# Sheet1.net
KiCad netlist of a schematic drawn in Altium Designer
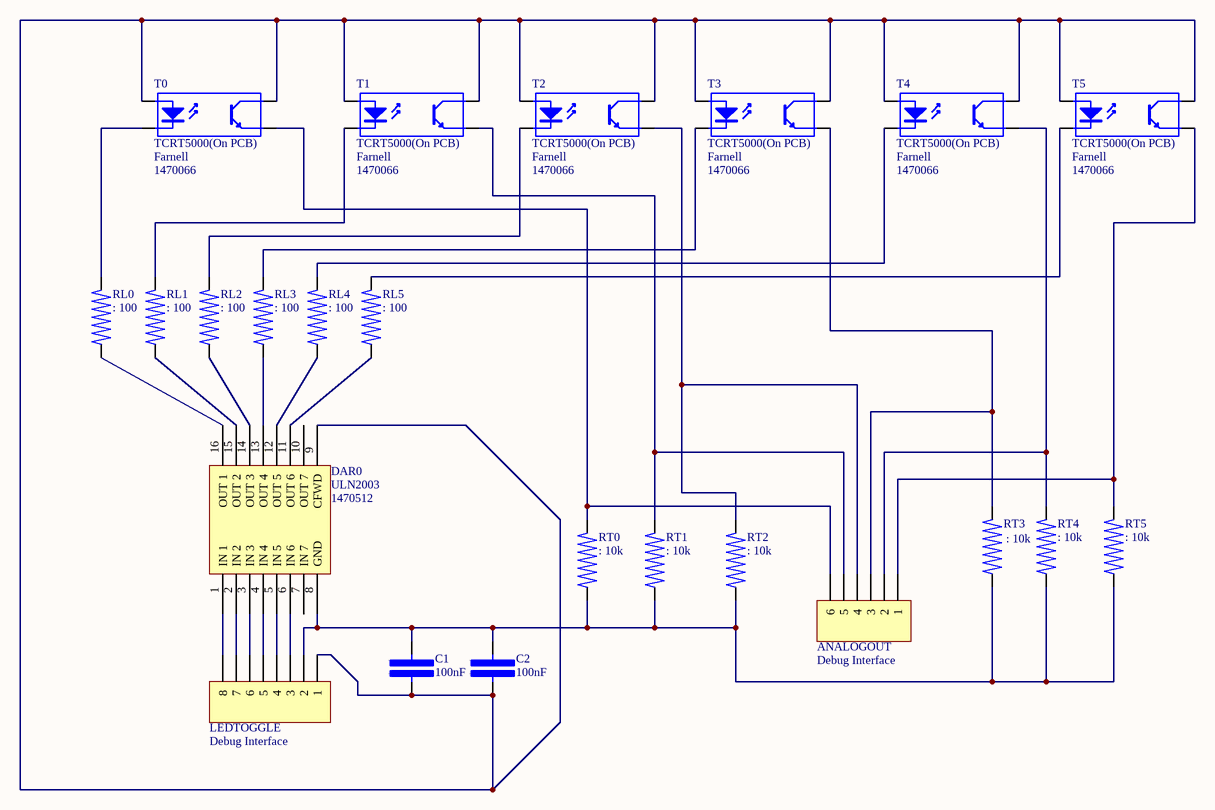
[diagram p0: Sheet1.SchDoc]

(export (version "E")
  (design (tool "Eeschema 10.0.6"))
  (components
    (comp (ref "ANALOGOUT")
      (value "Debug Interface")
      (footprint "PROGRAMMING-HEADER-MICRO")
      (description "Header, 6-Pin")
      (fields (field (name "PUBLISHER") "Altium Limited"))
      (libsource (lib "Integrated_Library") (part "Header 6"))
    )
    (comp (ref "C1")
      (value "100nF")
      (footprint "CAPACITOR_100NF_TH")
      (description "Capacitor 100nF")
      (libsource (lib "Integrated_Library") (part "Capacitor(IO Board)"))
    )
    (comp (ref "C2")
      (value "100nF")
      (footprint "CAPACITOR_100NF_TH")
      (description "Capacitor 100nF")
      (libsource (lib "Integrated_Library") (part "Capacitor(IO Board)"))
    )
    (comp (ref "DAR0")
      (value "ULN2003")
      (footprint "DILP-16(300) - 3D")
      (description "Darlington Transistor Array")
      (fields (field (name "SUPPLIER PART NUMBER 1") "1470512"))
      (libsource (lib "Integrated_Library") (part "ULN2003"))
    )
    (comp (ref "LEDTOGGLE")
      (value "Debug Interface")
      (footprint "HDR1X8")
      (description "Header, 8-Pin")
      (fields (field (name "PUBLISHER") "Altium Limited"))
      (libsource (lib "Miscellaneous Connectors") (part "Header 8"))
    )
    (comp (ref "RL0")
      (value "Resistor (IO board)")
      (footprint "RESISTOR_10K_TH_QW")
      (description "Resistor (SFR25)")
      (fields (field (name "ALTIUM_UNNAMED_1") "100"))
      (libsource (lib "Integrated_Library") (part "Resistor(IO board)"))
    )
    (comp (ref "RL1")
      (value "Resistor (IO board)")
      (footprint "RESISTOR_10K_TH_QW")
      (description "Resistor (SFR25)")
      (fields (field (name "ALTIUM_UNNAMED_1") "100"))
      (libsource (lib "Integrated_Library") (part "Resistor(IO board)"))
    )
    (comp (ref "RL2")
      (value "Resistor (IO board)")
      (footprint "RESISTOR_10K_TH_QW")
      (description "Resistor (SFR25)")
      (fields (field (name "ALTIUM_UNNAMED_1") "100"))
      (libsource (lib "Integrated_Library") (part "Resistor(IO board)"))
    )
    (comp (ref "RL3")
      (value "Resistor (IO board)")
      (footprint "RESISTOR_10K_TH_QW")
      (description "Resistor (SFR25)")
      (fields (field (name "ALTIUM_UNNAMED_1") "100"))
      (libsource (lib "Integrated_Library") (part "Resistor(IO board)"))
    )
    (comp (ref "RL4")
      (value "Resistor (IO board)")
      (footprint "RESISTOR_10K_TH_QW")
      (description "Resistor (SFR25)")
      (fields (field (name "ALTIUM_UNNAMED_1") "100"))
      (libsource (lib "Integrated_Library") (part "Resistor(IO board)"))
    )
    (comp (ref "RL5")
      (value "Resistor (IO board)")
      (footprint "RESISTOR_10K_TH_QW")
      (description "Resistor (SFR25)")
      (fields (field (name "ALTIUM_UNNAMED_1") "100"))
      (libsource (lib "Integrated_Library") (part "Resistor(IO board)"))
    )
    (comp (ref "RT0")
      (value "Resistor (IO board)")
      (footprint "RESISTOR_10K_TH_QW")
      (description "Resistor (SFR25)")
      (fields (field (name "ALTIUM_UNNAMED_1") "10k"))
      (libsource (lib "Integrated_Library") (part "Resistor(IO board)"))
    )
    (comp (ref "RT1")
      (value "Resistor (IO board)")
      (footprint "RESISTOR_10K_TH_QW")
      (description "Resistor (SFR25)")
      (fields (field (name "ALTIUM_UNNAMED_1") "10k"))
      (libsource (lib "Integrated_Library") (part "Resistor(IO board)"))
    )
    (comp (ref "RT2")
      (value "Resistor (IO board)")
      (footprint "RESISTOR_10K_TH_QW")
      (description "Resistor (SFR25)")
      (fields (field (name "ALTIUM_UNNAMED_1") "10k"))
      (libsource (lib "Integrated_Library") (part "Resistor(IO board)"))
    )
    (comp (ref "RT3")
      (value "Resistor (IO board)")
      (footprint "RESISTOR_10K_TH_QW")
      (description "Resistor (SFR25)")
      (fields (field (name "ALTIUM_UNNAMED_1") "10k"))
      (libsource (lib "Integrated_Library") (part "Resistor(IO board)"))
    )
    (comp (ref "RT4")
      (value "Resistor (IO board)")
      (footprint "RESISTOR_10K_TH_QW")
      (description "Resistor (SFR25)")
      (fields (field (name "ALTIUM_UNNAMED_1") "10k"))
      (libsource (lib "Integrated_Library") (part "Resistor(IO board)"))
    )
    (comp (ref "RT5")
      (value "Resistor (IO board)")
      (footprint "RESISTOR_10K_TH_QW")
      (description "Resistor (SFR25)")
      (fields (field (name "ALTIUM_UNNAMED_1") "10k"))
      (libsource (lib "Integrated_Library") (part "Resistor(IO board)"))
    )
    (comp (ref "T0")
      (value "TCRT5000(On PCB)")
      (footprint "TCRT5000 Breakout")
      (description "4-Pin Phototransistor Optocoupler")
      (fields
        (field (name "SUPPLIER 1") "Farnell")
        (field (name "SUPPLIER PART NUMBER 1") "1470066")
        (field (name "PUBLISHER") "Altium Limited")
      )
      (libsource (lib "Integrated_Library") (part "TCRT5000(On PCB)"))
    )
    (comp (ref "T1")
      (value "TCRT5000(On PCB)")
      (footprint "TCRT5000 Breakout")
      (description "4-Pin Phototransistor Optocoupler")
      (fields
        (field (name "SUPPLIER 1") "Farnell")
        (field (name "SUPPLIER PART NUMBER 1") "1470066")
        (field (name "PUBLISHER") "Altium Limited")
      )
      (libsource (lib "Integrated_Library") (part "TCRT5000(On PCB)"))
    )
    (comp (ref "T2")
      (value "TCRT5000(On PCB)")
      (footprint "TCRT5000 Breakout")
      (description "4-Pin Phototransistor Optocoupler")
      (fields
        (field (name "SUPPLIER 1") "Farnell")
        (field (name "SUPPLIER PART NUMBER 1") "1470066")
        (field (name "PUBLISHER") "Altium Limited")
      )
      (libsource (lib "Integrated_Library") (part "TCRT5000(On PCB)"))
    )
    (comp (ref "T3")
      (value "TCRT5000(On PCB)")
      (footprint "TCRT5000 Breakout")
      (description "4-Pin Phototransistor Optocoupler")
      (fields
        (field (name "SUPPLIER 1") "Farnell")
        (field (name "SUPPLIER PART NUMBER 1") "1470066")
        (field (name "PUBLISHER") "Altium Limited")
      )
      (libsource (lib "Integrated_Library") (part "TCRT5000(On PCB)"))
    )
    (comp (ref "T4")
      (value "TCRT5000(On PCB)")
      (footprint "TCRT5000 Breakout")
      (description "4-Pin Phototransistor Optocoupler")
      (fields
        (field (name "SUPPLIER 1") "Farnell")
        (field (name "SUPPLIER PART NUMBER 1") "1470066")
        (field (name "PUBLISHER") "Altium Limited")
      )
      (libsource (lib "Integrated_Library") (part "TCRT5000(On PCB)"))
    )
    (comp (ref "T5")
      (value "TCRT5000(On PCB)")
      (footprint "TCRT5000 Breakout")
      (description "4-Pin Phototransistor Optocoupler")
      (fields
        (field (name "SUPPLIER 1") "Farnell")
        (field (name "SUPPLIER PART NUMBER 1") "1470066")
        (field (name "PUBLISHER") "Altium Limited")
      )
      (libsource (lib "Integrated_Library") (part "TCRT5000(On PCB)"))
    )
  )
  (nets
    (net (code "1") (name "Net-(DAR0-CFWD)") (class "Default")
      (node (ref "C1") (pin "1") (pinfunction "1_1") (pintype "passive"))
      (node (ref "C2") (pin "1") (pinfunction "1_1") (pintype "passive"))
      (node (ref "DAR0") (pin "9") (pinfunction "CFWD_9") (pintype "passive"))
      (node (ref "LEDTOGGLE") (pin "1") (pinfunction "1_1") (pintype "passive"))
      (node (ref "T0") (pin "1") (pinfunction "A_1") (pintype "passive"))
      (node (ref "T0") (pin "4") (pinfunction "C_4") (pintype "passive"))
      (node (ref "T1") (pin "1") (pinfunction "A_1") (pintype "passive"))
      (node (ref "T1") (pin "4") (pinfunction "C_4") (pintype "passive"))
      (node (ref "T2") (pin "1") (pinfunction "A_1") (pintype "passive"))
      (node (ref "T2") (pin "4") (pinfunction "C_4") (pintype "passive"))
      (node (ref "T3") (pin "1") (pinfunction "A_1") (pintype "passive"))
      (node (ref "T3") (pin "4") (pinfunction "C_4") (pintype "passive"))
      (node (ref "T4") (pin "1") (pinfunction "A_1") (pintype "passive"))
      (node (ref "T4") (pin "4") (pinfunction "C_4") (pintype "passive"))
      (node (ref "T5") (pin "1") (pinfunction "A_1") (pintype "passive"))
      (node (ref "T5") (pin "4") (pinfunction "C_4") (pintype "passive"))
    )
    (net (code "2") (name "Net-(DAR0-GND)") (class "Default")
      (node (ref "C1") (pin "2") (pinfunction "2_2") (pintype "passive"))
      (node (ref "C2") (pin "2") (pinfunction "2_2") (pintype "passive"))
      (node (ref "DAR0") (pin "8") (pinfunction "GND_8") (pintype "passive"))
      (node (ref "LEDTOGGLE") (pin "2") (pinfunction "2_2") (pintype "passive"))
      (node (ref "RT0") (pin "1") (pinfunction "1_1") (pintype "passive"))
      (node (ref "RT1") (pin "1") (pinfunction "1_1") (pintype "passive"))
      (node (ref "RT2") (pin "1") (pinfunction "1_1") (pintype "passive"))
      (node (ref "RT3") (pin "1") (pinfunction "1_1") (pintype "passive"))
      (node (ref "RT4") (pin "1") (pinfunction "1_1") (pintype "passive"))
      (node (ref "RT5") (pin "1") (pinfunction "1_1") (pintype "passive"))
    )
    (net (code "3") (name "Net-(DAR0-IN_1)") (class "Default")
      (node (ref "DAR0") (pin "1") (pinfunction "IN_1_1") (pintype "passive"))
      (node (ref "LEDTOGGLE") (pin "8") (pinfunction "8_8") (pintype "passive"))
    )
    (net (code "4") (name "Net-(DAR0-IN_2)") (class "Default")
      (node (ref "DAR0") (pin "2") (pinfunction "IN_2_2") (pintype "passive"))
      (node (ref "LEDTOGGLE") (pin "7") (pinfunction "7_7") (pintype "passive"))
    )
    (net (code "5") (name "Net-(DAR0-IN_3)") (class "Default")
      (node (ref "DAR0") (pin "3") (pinfunction "IN_3_3") (pintype "passive"))
      (node (ref "LEDTOGGLE") (pin "6") (pinfunction "6_6") (pintype "passive"))
    )
    (net (code "6") (name "Net-(DAR0-IN_4)") (class "Default")
      (node (ref "DAR0") (pin "4") (pinfunction "IN_4_4") (pintype "passive"))
      (node (ref "LEDTOGGLE") (pin "5") (pinfunction "5_5") (pintype "passive"))
    )
    (net (code "7") (name "Net-(DAR0-IN_5)") (class "Default")
      (node (ref "DAR0") (pin "5") (pinfunction "IN_5_5") (pintype "passive"))
      (node (ref "LEDTOGGLE") (pin "4") (pinfunction "4_4") (pintype "passive"))
    )
    (net (code "8") (name "Net-(DAR0-IN_6)") (class "Default")
      (node (ref "DAR0") (pin "6") (pinfunction "IN_6_6") (pintype "passive"))
      (node (ref "LEDTOGGLE") (pin "3") (pinfunction "3_3") (pintype "passive"))
    )
    (net (code "9") (name "Net-(DAR0-OUT_1)") (class "Default")
      (node (ref "DAR0") (pin "16") (pinfunction "OUT_1_16") (pintype "passive"))
      (node (ref "RL0") (pin "1") (pinfunction "1_1") (pintype "passive"))
    )
    (net (code "10") (name "Net-(DAR0-OUT_2)") (class "Default")
      (node (ref "DAR0") (pin "15") (pinfunction "OUT_2_15") (pintype "passive"))
      (node (ref "RL1") (pin "1") (pinfunction "1_1") (pintype "passive"))
    )
    (net (code "11") (name "Net-(DAR0-OUT_3)") (class "Default")
      (node (ref "DAR0") (pin "14") (pinfunction "OUT_3_14") (pintype "passive"))
      (node (ref "RL2") (pin "1") (pinfunction "1_1") (pintype "passive"))
    )
    (net (code "12") (name "Net-(DAR0-OUT_4)") (class "Default")
      (node (ref "DAR0") (pin "13") (pinfunction "OUT_4_13") (pintype "passive"))
      (node (ref "RL3") (pin "1") (pinfunction "1_1") (pintype "passive"))
    )
    (net (code "13") (name "Net-(DAR0-OUT_5)") (class "Default")
      (node (ref "DAR0") (pin "12") (pinfunction "OUT_5_12") (pintype "passive"))
      (node (ref "RL4") (pin "1") (pinfunction "1_1") (pintype "passive"))
    )
    (net (code "14") (name "Net-(DAR0-OUT_6)") (class "Default")
      (node (ref "DAR0") (pin "11") (pinfunction "OUT_6_11") (pintype "passive"))
      (node (ref "RL5") (pin "1") (pinfunction "1_1") (pintype "passive"))
    )
    (net (code "15") (name "Net-(T0-E)") (class "Default")
      (node (ref "ANALOGOUT") (pin "6") (pinfunction "6_6") (pintype "passive"))
      (node (ref "RT0") (pin "2") (pinfunction "2_2") (pintype "passive"))
      (node (ref "T0") (pin "3") (pinfunction "E_3") (pintype "passive"))
    )
    (net (code "16") (name "Net-(T0-K)") (class "Default")
      (node (ref "RL0") (pin "2") (pinfunction "2_2") (pintype "passive"))
      (node (ref "T0") (pin "2") (pinfunction "K_2") (pintype "passive"))
    )
    (net (code "17") (name "Net-(T1-E)") (class "Default")
      (node (ref "ANALOGOUT") (pin "5") (pinfunction "5_5") (pintype "passive"))
      (node (ref "RT1") (pin "2") (pinfunction "2_2") (pintype "passive"))
      (node (ref "T1") (pin "3") (pinfunction "E_3") (pintype "passive"))
    )
    (net (code "18") (name "Net-(T1-K)") (class "Default")
      (node (ref "RL1") (pin "2") (pinfunction "2_2") (pintype "passive"))
      (node (ref "T1") (pin "2") (pinfunction "K_2") (pintype "passive"))
    )
    (net (code "19") (name "Net-(T2-E)") (class "Default")
      (node (ref "ANALOGOUT") (pin "4") (pinfunction "4_4") (pintype "passive"))
      (node (ref "RT2") (pin "2") (pinfunction "2_2") (pintype "passive"))
      (node (ref "T2") (pin "3") (pinfunction "E_3") (pintype "passive"))
    )
    (net (code "20") (name "Net-(T2-K)") (class "Default")
      (node (ref "RL2") (pin "2") (pinfunction "2_2") (pintype "passive"))
      (node (ref "T2") (pin "2") (pinfunction "K_2") (pintype "passive"))
    )
    (net (code "21") (name "Net-(T3-E)") (class "Default")
      (node (ref "ANALOGOUT") (pin "3") (pinfunction "3_3") (pintype "passive"))
      (node (ref "RT3") (pin "2") (pinfunction "2_2") (pintype "passive"))
      (node (ref "T3") (pin "3") (pinfunction "E_3") (pintype "passive"))
    )
    (net (code "22") (name "Net-(T3-K)") (class "Default")
      (node (ref "RL3") (pin "2") (pinfunction "2_2") (pintype "passive"))
      (node (ref "T3") (pin "2") (pinfunction "K_2") (pintype "passive"))
    )
    (net (code "23") (name "Net-(T4-E)") (class "Default")
      (node (ref "ANALOGOUT") (pin "2") (pinfunction "2_2") (pintype "passive"))
      (node (ref "RT4") (pin "2") (pinfunction "2_2") (pintype "passive"))
      (node (ref "T4") (pin "3") (pinfunction "E_3") (pintype "passive"))
    )
    (net (code "24") (name "Net-(T4-K)") (class "Default")
      (node (ref "RL4") (pin "2") (pinfunction "2_2") (pintype "passive"))
      (node (ref "T4") (pin "2") (pinfunction "K_2") (pintype "passive"))
    )
    (net (code "25") (name "Net-(T5-E)") (class "Default")
      (node (ref "ANALOGOUT") (pin "1") (pinfunction "1_1") (pintype "passive"))
      (node (ref "RT5") (pin "2") (pinfunction "2_2") (pintype "passive"))
      (node (ref "T5") (pin "3") (pinfunction "E_3") (pintype "passive"))
    )
    (net (code "26") (name "Net-(T5-K)") (class "Default")
      (node (ref "RL5") (pin "2") (pinfunction "2_2") (pintype "passive"))
      (node (ref "T5") (pin "2") (pinfunction "K_2") (pintype "passive"))
    )
    (net (code "27") (name "unconnected-(DAR0-IN_7-Pad7)") (class "Default")
      (node (ref "DAR0") (pin "7") (pinfunction "IN_7_7") (pintype "passive"))
    )
    (net (code "28") (name "unconnected-(DAR0-OUT_7-Pad10)") (class "Default")
      (node (ref "DAR0") (pin "10") (pinfunction "OUT_7_10") (pintype "passive"))
    )
  )
)
